# SCH_PCB-ROCKET-1_2024-09-01.net
KiCad netlist of a schematic drawn in EasyEDA
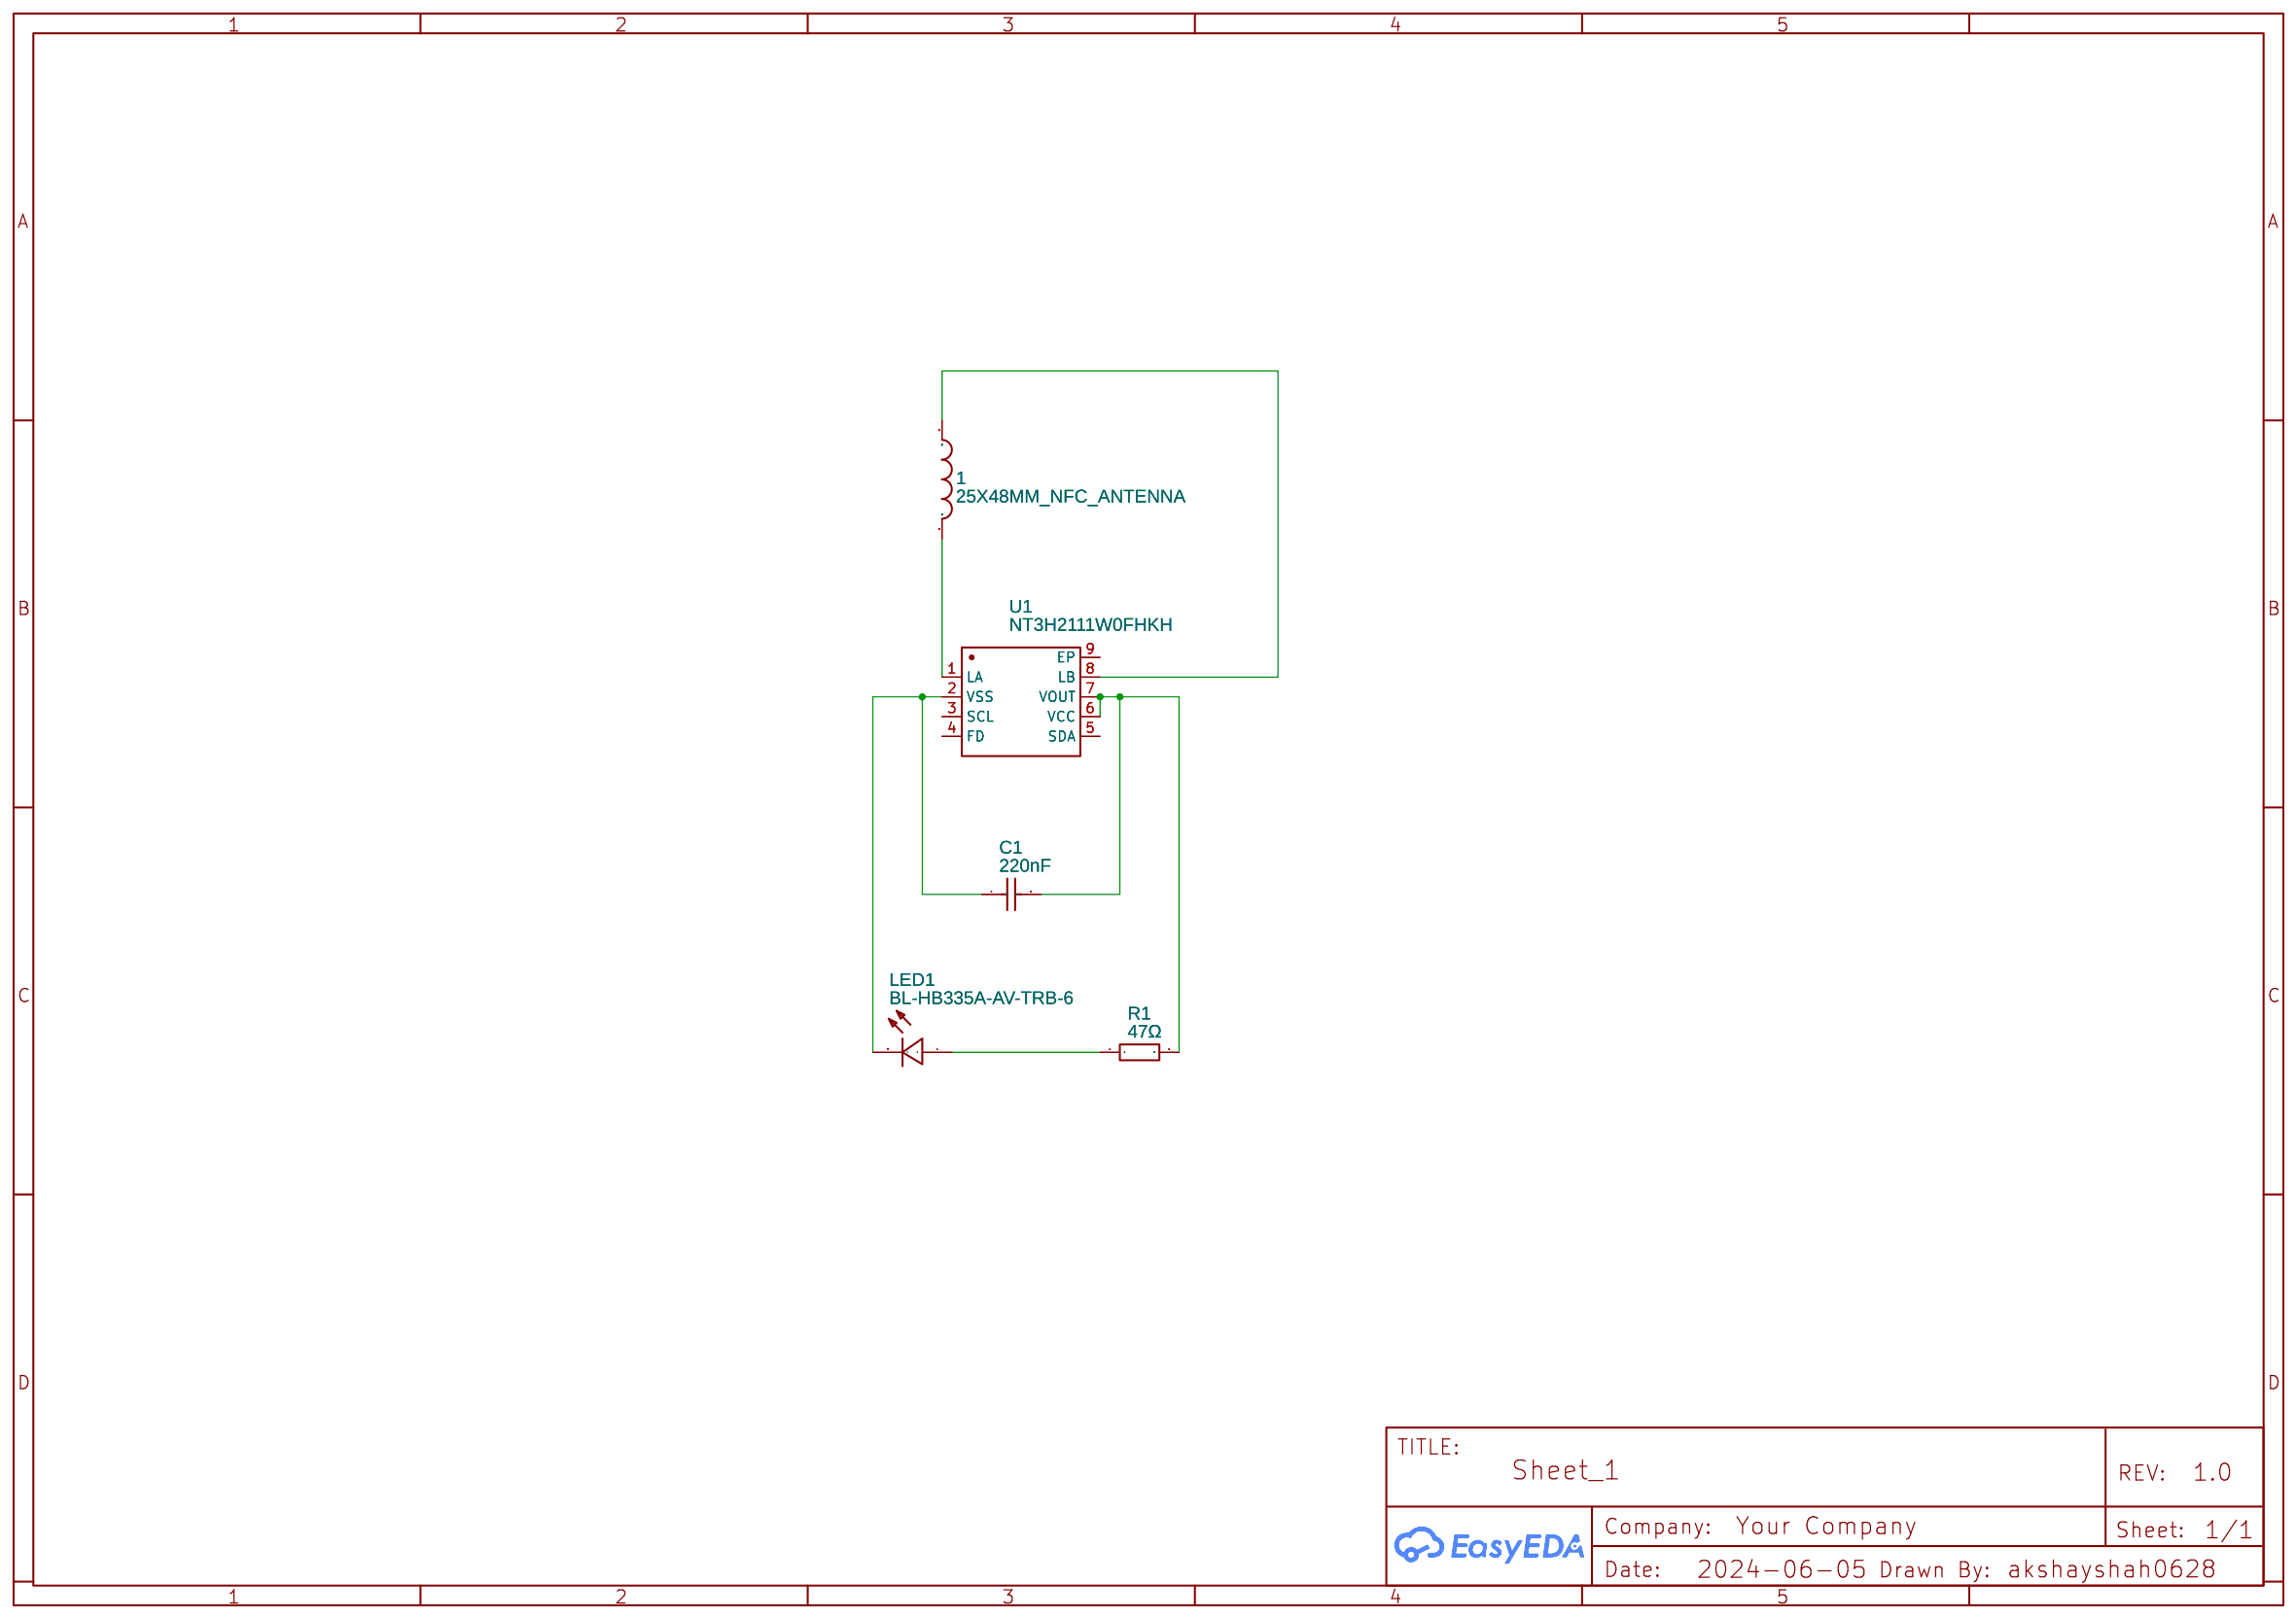
[diagram p0: schematic sheet]

(export (version "E")
  (design (tool "Eeschema 10.0.6"))
  (components
    (comp (ref "1") (value "25X48MM_NFC_ANTENNA") (libsource (lib "") (part "25X48MM_NFC_ANTENNA")))
    (comp (ref "C1")
      (value "220nF")
      (fields
        (field (name "Manufacturer Part") "CL10B224KA8NNNC")
        (field (name "Manufacturer") "SAMSUNG(三星)")
      )
      (libsource (lib "") (part "CL10B224KA8NNNC"))
    )
    (comp (ref "LED1")
      (value "BL-HB335A-AV-TRB-6")
      (fields (field (name "Manufacturer") "BrtLed(佰鸿)"))
      (libsource (lib "") (part "BL-HB335A-AV-TRB-6"))
    )
    (comp (ref "R1")
      (value "47Ω")
      (fields
        (field (name "Manufacturer Part") "0603WAF470JT5E")
        (field (name "Manufacturer") "UNI-ROYAL(厚声)")
      )
      (libsource (lib "") (part "0603WAF470JT5E"))
    )
    (comp (ref "U1")
      (value "NT3H2111W0FHKH")
      (fields (field (name "Manufacturer") "NXP(恩智浦)"))
      (libsource (lib "") (part "NT3H2111W0FHKH"))
    )
  )
  (nets
    (net (code "1") (name "Net-(LED1-+)") (class "Default")
      (node (ref "LED1") (pin "1") (pinfunction "+_1") (pintype "unspecified"))
      (node (ref "R1") (pin "1") (pinfunction "1_1") (pintype "input"))
    )
    (net (code "2") (name "Net-(LED1--)") (class "Default")
      (node (ref "C1") (pin "1") (pinfunction "1_1") (pintype "input"))
      (node (ref "LED1") (pin "2") (pinfunction "-_2") (pintype "unspecified"))
      (node (ref "U1") (pin "2") (pinfunction "VSS_2") (pintype "unspecified"))
    )
    (net (code "3") (name "Net-(U1-LA)") (class "Default")
      (node (ref "1") (pin "P$2") (pinfunction "P$2_P$2") (pintype "bidirectional"))
      (node (ref "U1") (pin "1") (pinfunction "LA_1") (pintype "unspecified"))
    )
    (net (code "4") (name "Net-(U1-LB)") (class "Default")
      (node (ref "1") (pin "P$1") (pinfunction "P$1_P$1") (pintype "bidirectional"))
      (node (ref "U1") (pin "8") (pinfunction "LB_8") (pintype "unspecified"))
    )
    (net (code "5") (name "Net-(U1-VCC)") (class "Default")
      (node (ref "C1") (pin "2") (pinfunction "2_2") (pintype "input"))
      (node (ref "R1") (pin "2") (pinfunction "2_2") (pintype "input"))
      (node (ref "U1") (pin "6") (pinfunction "VCC_6") (pintype "unspecified"))
      (node (ref "U1") (pin "7") (pinfunction "VOUT_7") (pintype "unspecified"))
    )
    (net (code "6") (name "unconnected-(U1-EP-Pad9)") (class "Default")
      (node (ref "U1") (pin "9") (pinfunction "EP_9") (pintype "unspecified"))
    )
    (net (code "7") (name "unconnected-(U1-FD-Pad4)") (class "Default")
      (node (ref "U1") (pin "4") (pinfunction "FD_4") (pintype "unspecified"))
    )
    (net (code "8") (name "unconnected-(U1-SCL-Pad3)") (class "Default")
      (node (ref "U1") (pin "3") (pinfunction "SCL_3") (pintype "unspecified"))
    )
    (net (code "9") (name "unconnected-(U1-SDA-Pad5)") (class "Default")
      (node (ref "U1") (pin "5") (pinfunction "SDA_5") (pintype "unspecified"))
    )
  )
)
